# BAT___PROTECTOR.net
KiCad netlist of a schematic drawn in Altium Designer
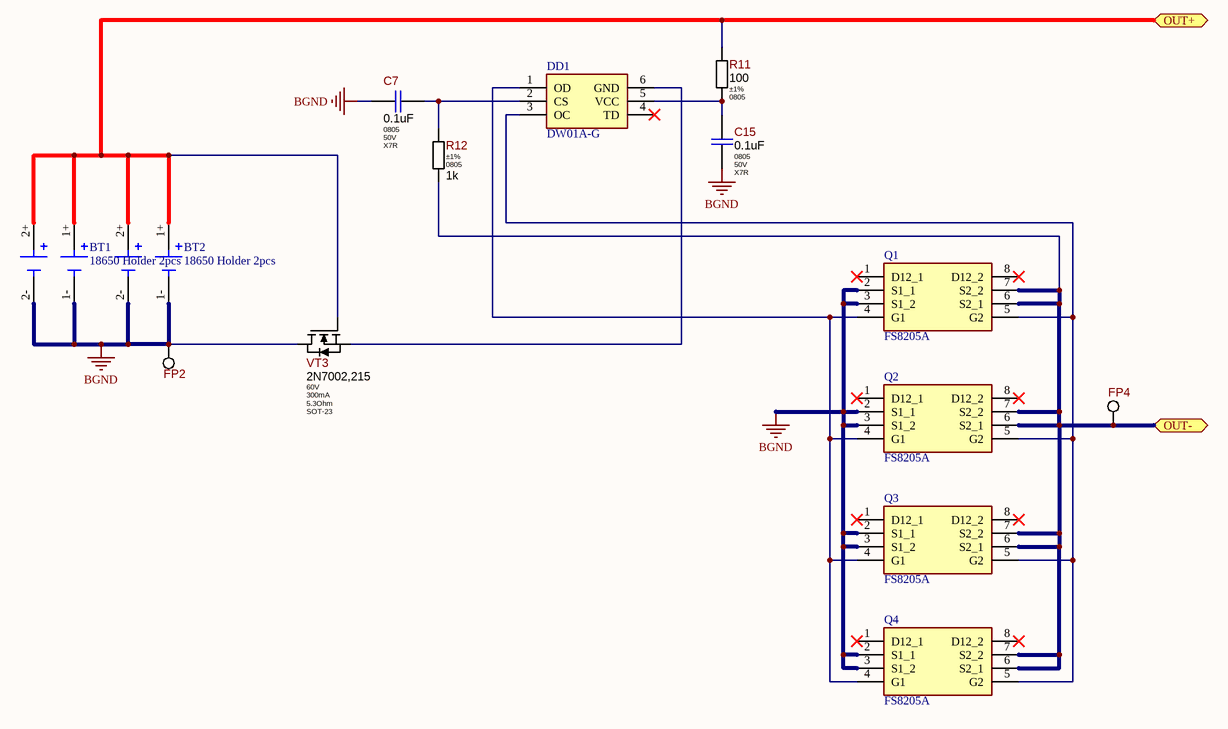
[diagram p0: BAT_&_PROTECTOR.SchDoc]

(export (version "E")
  (design (tool "Eeschema 10.0.6"))
  (components
    (comp (ref "BT1")
      (value "18650 Holder 2pcs")
      (footprint "BAT_BK-18650-PC4")
      (description "Battery Holder (Open) 18650 2 Cell PC Pin")
      (fields (field (name "MP") "BK-18650-PC4"))
      (libsource (lib "vitech_lib") (part "18650 Holder 2pcs"))
    )
    (comp (ref "BT2")
      (value "18650 Holder 2pcs")
      (footprint "BAT_BK-18650-PC4")
      (description "Battery Holder (Open) 18650 2 Cell PC Pin")
      (fields (field (name "MP") "BK-18650-PC4"))
      (libsource (lib "vitech_lib") (part "18650 Holder 2pcs"))
    )
    (comp (ref "C7")
      (value "0.1uF")
      (footprint "CAP-0805(2012)X85T10")
      (description "100nF 50V X7R ±10% 0805 Ceramic Capacitor RoHS")
      (fields
        (field (name "PACKAGE") "0805")
        (field (name "VOLTAGE") "50V")
        (field (name "DIELECTRIC TYPE") "X7R")
        (field (name "PART NUMBER") "CL21B104KBCNNNC")
        (field (name "MANUFACTURER") "Samsung Electro-Mechanics")
      )
      (libsource (lib "capacitors") (part "CL21B104KBCNNNC"))
    )
    (comp (ref "C15")
      (value "0.1uF")
      (footprint "CAP-0805(2012)X85T10")
      (description "100nF 50V X7R ±10% 0805 Ceramic Capacitor RoHS")
      (fields
        (field (name "PACKAGE") "0805")
        (field (name "VOLTAGE") "50V")
        (field (name "DIELECTRIC TYPE") "X7R")
        (field (name "PART NUMBER") "CL21B104KBCNNNC")
        (field (name "MANUFACTURER") "Samsung Electro-Mechanics")
      )
      (libsource (lib "capacitors") (part "CL21B104KBCNNNC"))
    )
    (comp (ref "DD1")
      (value "DW01A-G")
      (footprint "DW01A-G")
      (description "One Cell Lithium-ion/Polymer Battery Protection IC")
      (libsource (lib "vitech_lib") (part "DW01A-G"))
    )
    (comp (ref "FP2")
      (value "PAD-1.45mm")
      (footprint "PAD-1.45mm")
      (description "1.45mm Pad for Plug-In or Receptacle")
      (fields (field (name "MANUFACTURER") "NONE"))
      (libsource (lib "probetools") (part "PAD-1.45mm"))
    )
    (comp (ref "FP4")
      (value "PAD-1.45mm")
      (footprint "PAD-1.45mm")
      (description "1.45mm Pad for Plug-In or Receptacle")
      (fields (field (name "MANUFACTURER") "NONE"))
      (libsource (lib "probetools") (part "PAD-1.45mm"))
    )
    (comp (ref "Q1")
      (value "FS8205A")
      (footprint "FS8205A")
      (description "Dual N-Channel Enahncement Mode Power MOSFET")
      (libsource (lib "vitech_lib") (part "FS8205A"))
    )
    (comp (ref "Q2")
      (value "FS8205A")
      (footprint "FS8205A")
      (description "Dual N-Channel Enahncement Mode Power MOSFET")
      (libsource (lib "vitech_lib") (part "FS8205A"))
    )
    (comp (ref "Q3")
      (value "FS8205A")
      (footprint "FS8205A")
      (description "Dual N-Channel Enahncement Mode Power MOSFET")
      (libsource (lib "vitech_lib") (part "FS8205A"))
    )
    (comp (ref "Q4")
      (value "FS8205A")
      (footprint "FS8205A")
      (description "Dual N-Channel Enahncement Mode Power MOSFET")
      (libsource (lib "vitech_lib") (part "FS8205A"))
    )
    (comp (ref "R11")
      (value "100")
      (footprint "R_ANY_CHIP_0805_MED")
      (description "100 Ohms ±1%, 1/8W 0805 Thick Film Resistor")
      (fields
        (field (name "TOLERANCE") "±1%")
        (field (name "PACKAGE") "0805")
        (field (name "PART NUMBER") "RC0805FR-07120RL")
        (field (name "MANUFACTURER") "Yageo")
      )
      (libsource (lib "resistors") (part "RC0805FR-07120RL"))
    )
    (comp (ref "R12")
      (value "1k")
      (footprint "R_ANY_CHIP_0805_MED")
      (description "1 kOhms ±1%, 1/8W 0805 Thick Film Resistor")
      (fields
        (field (name "TOLERANCE") "±1%")
        (field (name "PACKAGE") "0805")
        (field (name "PART NUMBER") "RC0805FR-071KL")
        (field (name "MANUFACTURER") "Yageo")
      )
      (libsource (lib "resistors") (part "RC0805FR-071KL"))
    )
    (comp (ref "VT3")
      (value "2N7002,215")
      (footprint "SOT-23_MED")
      (description "60V, 300mA max N-Channel Trench MOSFET, 3.8Ohm @ Vgs = 4.5V")
      (fields
        (field (name "PART NUMBER") "2N7002,215")
        (field (name "VDS") "60V")
        (field (name "ID") "300mA")
        (field (name "RDS") "5.3Ohm")
        (field (name "PACKAGE") "SOT-23")
        (field (name "MANUFACTURER") "Nexperia USA")
      )
      (libsource (lib "transistors") (part "2N7002,215"))
    )
  )
  (nets
    (net (code "1") (name "/OUT+") (class "Default")
      (node (ref "BT1") (pin "1+") (pinfunction "1+_1+") (pintype "passive"))
      (node (ref "BT1") (pin "2+") (pinfunction "2+_2+") (pintype "passive"))
      (node (ref "BT2") (pin "1+") (pinfunction "1+_1+") (pintype "passive"))
      (node (ref "BT2") (pin "2+") (pinfunction "2+_2+") (pintype "passive"))
      (node (ref "R11") (pin "2") (pintype "passive"))
      (node (ref "VT3") (pin "1") (pinfunction "G_1") (pintype "passive"))
    )
    (net (code "2") (name "/OUT-") (class "Default")
      (node (ref "FP4") (pin "1") (pintype "passive"))
      (node (ref "Q1") (pin "6") (pinfunction "S2_1_6") (pintype "passive"))
      (node (ref "Q1") (pin "7") (pinfunction "S2_2_7") (pintype "passive"))
      (node (ref "Q2") (pin "6") (pinfunction "S2_1_6") (pintype "passive"))
      (node (ref "Q2") (pin "7") (pinfunction "S2_2_7") (pintype "passive"))
      (node (ref "Q3") (pin "6") (pinfunction "S2_1_6") (pintype "passive"))
      (node (ref "Q3") (pin "7") (pinfunction "S2_2_7") (pintype "passive"))
      (node (ref "Q4") (pin "6") (pinfunction "S2_1_6") (pintype "passive"))
      (node (ref "Q4") (pin "7") (pinfunction "S2_2_7") (pintype "passive"))
      (node (ref "R12") (pin "1") (pintype "passive"))
    )
    (net (code "3") (name "BGND") (class "Default")
      (node (ref "BT1") (pin "1-") (pinfunction "1-_1-") (pintype "passive"))
      (node (ref "BT1") (pin "2-") (pinfunction "2-_2-") (pintype "passive"))
      (node (ref "BT2") (pin "1-") (pinfunction "1-_1-") (pintype "passive"))
      (node (ref "BT2") (pin "2-") (pinfunction "2-_2-") (pintype "passive"))
      (node (ref "C15") (pin "1") (pinfunction "1_1") (pintype "passive"))
      (node (ref "C7") (pin "1") (pinfunction "1_1") (pintype "passive"))
      (node (ref "FP2") (pin "1") (pintype "passive"))
      (node (ref "Q1") (pin "2") (pinfunction "S1_1_2") (pintype "passive"))
      (node (ref "Q1") (pin "3") (pinfunction "S1_2_3") (pintype "passive"))
      (node (ref "Q2") (pin "2") (pinfunction "S1_1_2") (pintype "passive"))
      (node (ref "Q2") (pin "3") (pinfunction "S1_2_3") (pintype "passive"))
      (node (ref "Q3") (pin "2") (pinfunction "S1_1_2") (pintype "passive"))
      (node (ref "Q3") (pin "3") (pinfunction "S1_2_3") (pintype "passive"))
      (node (ref "Q4") (pin "2") (pinfunction "S1_1_2") (pintype "passive"))
      (node (ref "Q4") (pin "3") (pinfunction "S1_2_3") (pintype "passive"))
      (node (ref "VT3") (pin "3") (pinfunction "D_3") (pintype "passive"))
    )
    (net (code "4") (name "Net-(DD1-CS)") (class "Default")
      (node (ref "C7") (pin "2") (pinfunction "2_2") (pintype "passive"))
      (node (ref "DD1") (pin "2") (pinfunction "CS_2") (pintype "passive"))
      (node (ref "R12") (pin "2") (pintype "passive"))
    )
    (net (code "5") (name "Net-(DD1-GND)") (class "Default")
      (node (ref "DD1") (pin "6") (pinfunction "GND_6") (pintype "passive"))
      (node (ref "VT3") (pin "2") (pinfunction "S_2") (pintype "passive"))
    )
    (net (code "6") (name "Net-(DD1-OC)") (class "Default")
      (node (ref "DD1") (pin "3") (pinfunction "OC_3") (pintype "passive"))
      (node (ref "Q1") (pin "5") (pinfunction "G2_5") (pintype "passive"))
      (node (ref "Q2") (pin "5") (pinfunction "G2_5") (pintype "passive"))
      (node (ref "Q3") (pin "5") (pinfunction "G2_5") (pintype "passive"))
      (node (ref "Q4") (pin "5") (pinfunction "G2_5") (pintype "passive"))
    )
    (net (code "7") (name "Net-(DD1-OD)") (class "Default")
      (node (ref "DD1") (pin "1") (pinfunction "OD_1") (pintype "passive"))
      (node (ref "Q1") (pin "4") (pinfunction "G1_4") (pintype "passive"))
      (node (ref "Q2") (pin "4") (pinfunction "G1_4") (pintype "passive"))
      (node (ref "Q3") (pin "4") (pinfunction "G1_4") (pintype "passive"))
      (node (ref "Q4") (pin "4") (pinfunction "G1_4") (pintype "passive"))
    )
    (net (code "8") (name "Net-(DD1-VCC)") (class "Default")
      (node (ref "C15") (pin "2") (pinfunction "2_2") (pintype "passive"))
      (node (ref "DD1") (pin "5") (pinfunction "VCC_5") (pintype "passive"))
      (node (ref "R11") (pin "1") (pintype "passive"))
    )
    (net (code "9") (name "unconnected-(DD1-TD-Pad4)") (class "Default")
      (node (ref "DD1") (pin "4") (pinfunction "TD_4") (pintype "passive+no_connect"))
    )
    (net (code "10") (name "unconnected-(Q1-D12_1-Pad1)") (class "Default")
      (node (ref "Q1") (pin "1") (pinfunction "D12_1_1") (pintype "passive+no_connect"))
    )
    (net (code "11") (name "unconnected-(Q1-D12_2-Pad8)") (class "Default")
      (node (ref "Q1") (pin "8") (pinfunction "D12_2_8") (pintype "passive+no_connect"))
    )
    (net (code "12") (name "unconnected-(Q2-D12_1-Pad1)") (class "Default")
      (node (ref "Q2") (pin "1") (pinfunction "D12_1_1") (pintype "passive+no_connect"))
    )
    (net (code "13") (name "unconnected-(Q2-D12_2-Pad8)") (class "Default")
      (node (ref "Q2") (pin "8") (pinfunction "D12_2_8") (pintype "passive+no_connect"))
    )
    (net (code "14") (name "unconnected-(Q3-D12_1-Pad1)") (class "Default")
      (node (ref "Q3") (pin "1") (pinfunction "D12_1_1") (pintype "passive+no_connect"))
    )
    (net (code "15") (name "unconnected-(Q3-D12_2-Pad8)") (class "Default")
      (node (ref "Q3") (pin "8") (pinfunction "D12_2_8") (pintype "passive+no_connect"))
    )
    (net (code "16") (name "unconnected-(Q4-D12_1-Pad1)") (class "Default")
      (node (ref "Q4") (pin "1") (pinfunction "D12_1_1") (pintype "passive+no_connect"))
    )
    (net (code "17") (name "unconnected-(Q4-D12_2-Pad8)") (class "Default")
      (node (ref "Q4") (pin "8") (pinfunction "D12_2_8") (pintype "passive+no_connect"))
    )
  )
)
